# HVAL_TSAL.net
KiCad netlist of a schematic drawn in Altium Designer
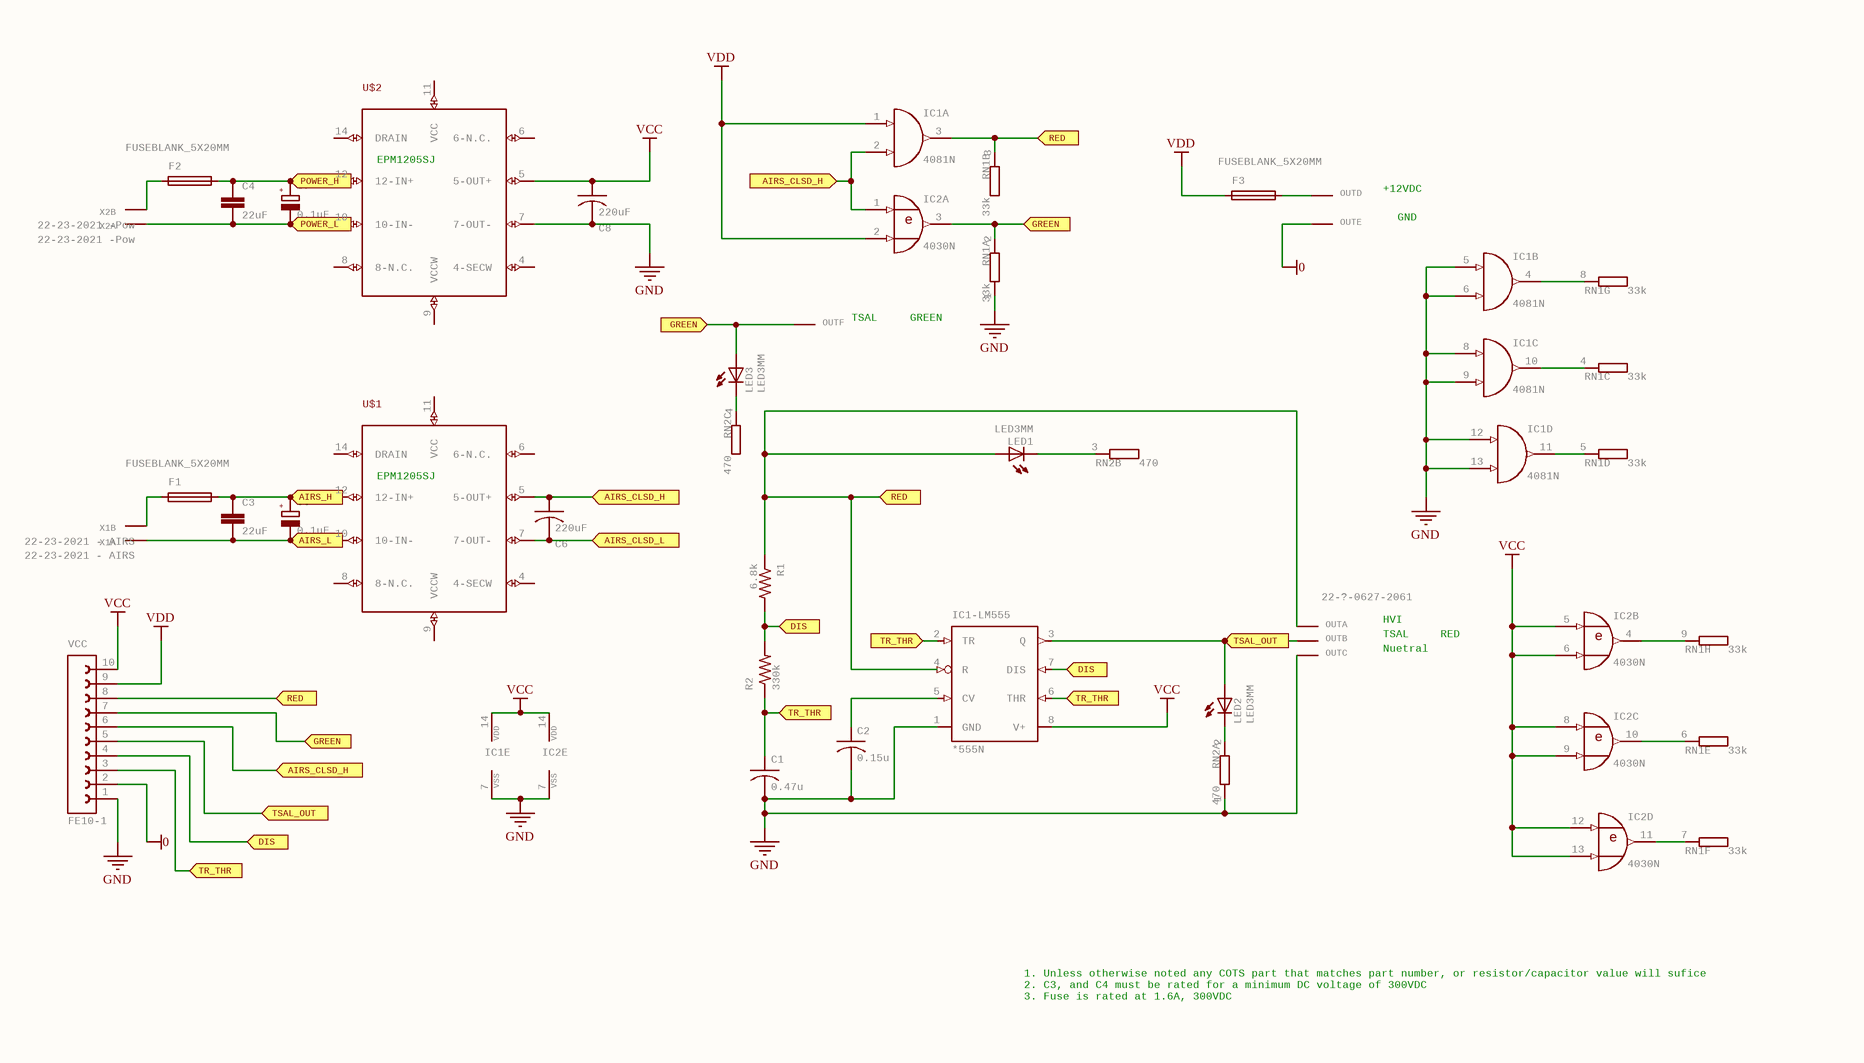
[diagram p0: HVAL_TSAL.SchDoc]

(export (version "E")
  (design (tool "Eeschema 10.0.6"))
  (components
    (comp (ref "C1")
      (value "0.47u")
      (footprint "C050-075X075")
      (description "CAPACITOR, American symbol")
      (libsource (lib "rcl") (part "C-US050-075X075"))
    )
    (comp (ref "C2")
      (value "0.15u")
      (footprint "C050-075X075")
      (description "CAPACITOR, American symbol")
      (libsource (lib "rcl") (part "C-US050-075X075"))
    )
    (comp (ref "C3")
      (value "22uF")
      (footprint "C150-091X182")
      (description "CAPACITOR, European symbol")
      (libsource (lib "rcl") (part "C-EU150-091X182"))
    )
    (comp (ref "C4")
      (value "22uF")
      (footprint "C150-091X182")
      (description "CAPACITOR, European symbol")
      (libsource (lib "rcl") (part "C-EU150-091X182"))
    )
    (comp (ref "C5")
      (value "0.1uF")
      (footprint "E7,5-16")
      (description "POLARIZED CAPACITOR, European symbol")
      (fields (field (name "+") "+"))
      (libsource (lib "rcl") (part "CPOL-EUE7.5-16"))
    )
    (comp (ref "C6")
      (value "220uF")
      (footprint "C050-055X075")
      (description "CAPACITOR, American symbol")
      (libsource (lib "rcl") (part "C-US050-055X075"))
    )
    (comp (ref "C7")
      (value "0.1uF")
      (footprint "E7,5-16")
      (description "POLARIZED CAPACITOR, European symbol")
      (fields (field (name "+") "+"))
      (libsource (lib "rcl") (part "CPOL-EUE7.5-16"))
    )
    (comp (ref "C8")
      (value "220uF")
      (footprint "C050-055X075")
      (description "CAPACITOR, American symbol")
      (libsource (lib "rcl") (part "C-US050-055X075"))
    )
    (comp (ref "F1")
      (value "FUSEBLANK_5X20MM")
      (footprint "FUSE_HOLDER_5X20MM")
      (description "Fuse")
      (fields (field (name "MF") "MF") (field (name "MPN") "MPN"))
      (libsource (lib "fuse") (part "FUSEBLANK_5X20MM"))
    )
    (comp (ref "F2")
      (value "FUSEBLANK_5X20MM")
      (footprint "FUSE_HOLDER_5X20MM")
      (description "Fuse")
      (fields (field (name "MF") "MF") (field (name "MPN") "MPN"))
      (libsource (lib "fuse") (part "FUSEBLANK_5X20MM"))
    )
    (comp (ref "F3")
      (value "FUSEBLANK_5X20MM")
      (footprint "FUSE_HOLDER_5X20MM")
      (description "Fuse")
      (fields (field (name "MF") "MF") (field (name "MPN") "MPN"))
      (libsource (lib "fuse") (part "FUSEBLANK_5X20MM"))
    )
    (comp (ref "IC1")
      (value "4081N")
      (footprint "DIL14")
      (description "Quad 2-input AND")
      (fields (field (name "VDD") "VDD") (field (name "VSS") "VSS"))
      (libsource (lib "40xx") (part "4081N"))
    )
    (comp (ref "IC1-LM555")
      (value "*555N")
      (footprint "DIL08")
      (description "TIMER")
      (libsource (lib "linear") (part "*555N"))
    )
    (comp (ref "IC2")
      (value "4030N")
      (footprint "DIL14")
      (description "Quad XOR")
      (fields (field (name "VDD") "VDD") (field (name "VSS") "VSS") (field (name "E") "e"))
      (libsource (lib "40xx") (part "4030N"))
    )
    (comp (ref "LED1") (value "LED3MM") (footprint "LED3MM") (libsource (lib "led") (part "LED3MM")))
    (comp (ref "LED2") (value "LED3MM") (footprint "LED3MM") (libsource (lib "led") (part "LED3MM")))
    (comp (ref "LED3") (value "LED3MM") (footprint "LED3MM") (libsource (lib "led") (part "LED3MM")))
    (comp (ref "OUT")
      (value "22-?-0627-2061")
      (footprint "6410-06")
      (description "CONNECTOR   wire to board 2.54 mm (.1 inch) pitch header")
      (fields (field (name "MF") "MOLEX") (field (name "MPN") "MPN"))
      (libsource (lib "con-molex") (part "22-?-0627-2061"))
    )
    (comp (ref "R1")
      (value "6.8k")
      (footprint "0309/12")
      (description "RESISTOR, American symbol")
      (libsource (lib "resistor") (part "R-US_0309/12"))
    )
    (comp (ref "R2")
      (value "330k")
      (footprint "0309/12")
      (description "RESISTOR, American symbol")
      (libsource (lib "resistor") (part "R-US_0309/12"))
    )
    (comp (ref "RN1")
      (value "33k")
      (footprint "SIL9")
      (description "SIL RESISTOR")
      (fields (field (name "MF") "MF") (field (name "MPN") "MPN"))
      (libsource (lib "resistor-sil") (part "GE08R"))
    )
    (comp (ref "RN2")
      (value "470")
      (footprint "SIL4")
      (description "SIL RESISTOR")
      (fields (field (name "MF") "MF") (field (name "MPN") "MPN"))
      (libsource (lib "resistor-sil") (part "GE03R"))
    )
    (comp (ref "U$1")
      (value "EPM1205SJ")
      (footprint "EPM1205SJ")
      (libsource (lib "DC-DC Converter") (part "EPM1205SJ"))
    )
    (comp (ref "U$2")
      (value "EPM1205SJ")
      (footprint "EPM1205SJ")
      (libsource (lib "DC-DC Converter") (part "EPM1205SJ"))
    )
    (comp (ref "VCC")
      (value "FE10-1")
      (footprint "FE10")
      (description "FEMALE HEADER")
      (fields (field (name "MF") "MF") (field (name "MPN") "MPN") (field (name "LIBRARYNAME") "con-lsta"))
      (libsource (lib "con-lsta") (part "FE10-1"))
    )
    (comp (ref "X1")
      (value "22-23-2021 - AIRS")
      (footprint "22-23-2021")
      (description ".100\" (2.54mm) Center Header - 2 Pin")
      (fields (field (name "MF") "MOLEX") (field (name "MPN") "22-23-2021"))
      (libsource (lib "con-molex") (part "22-23-2021"))
    )
    (comp (ref "X2")
      (value "22-23-2021 -Pow")
      (footprint "22-23-2021")
      (description ".100\" (2.54mm) Center Header - 2 Pin")
      (fields (field (name "MF") "MOLEX") (field (name "MPN") "22-23-2021"))
      (libsource (lib "con-molex") (part "22-23-2021"))
    )
  )
  (nets
    (net (code "1") (name "/AIRS_CLSD_H") (class "Default")
      (node (ref "C6") (pin "1") (pinfunction "1_1") (pintype "passive"))
      (node (ref "IC1") (pin "2") (pinfunction "I1_2") (pintype "input"))
      (node (ref "IC2") (pin "1") (pinfunction "I0_1") (pintype "input"))
      (node (ref "U$1") (pin "5") (pinfunction "5-OUT+_5") (pintype "bidirectional"))
      (node (ref "VCC") (pin "6") (pinfunction "6_6") (pintype "passive"))
    )
    (net (code "2") (name "/AIRS_CLSD_L") (class "Default")
      (node (ref "C6") (pin "2") (pinfunction "2_2") (pintype "passive"))
      (node (ref "U$1") (pin "7") (pinfunction "7-OUT-_7") (pintype "bidirectional"))
    )
    (net (code "3") (name "/AIRS_H") (class "Default")
      (node (ref "C3") (pin "1") (pinfunction "1_1") (pintype "passive"))
      (node (ref "C5") (pin "+") (pinfunction "+_+") (pintype "passive"))
      (node (ref "F1") (pin "2") (pinfunction "2_2") (pintype "passive"))
      (node (ref "U$1") (pin "12") (pinfunction "12-IN+_12") (pintype "bidirectional"))
    )
    (net (code "4") (name "/AIRS_L") (class "Default")
      (node (ref "C3") (pin "2") (pinfunction "2_2") (pintype "passive"))
      (node (ref "C5") (pin "-") (pinfunction "-_-") (pintype "passive"))
      (node (ref "U$1") (pin "10") (pinfunction "10-IN-_10") (pintype "bidirectional"))
      (node (ref "X1") (pin "1") (pinfunction "S_1") (pintype "passive"))
    )
    (net (code "5") (name "/DIS") (class "Default")
      (node (ref "IC1-LM555") (pin "7") (pinfunction "DIS_7") (pintype "input"))
      (node (ref "R1") (pin "2") (pinfunction "2_2") (pintype "passive"))
      (node (ref "R2") (pin "2") (pinfunction "2_2") (pintype "passive"))
      (node (ref "VCC") (pin "4") (pinfunction "4_4") (pintype "passive"))
    )
    (net (code "6") (name "/GREEN") (class "Default")
      (node (ref "IC2") (pin "3") (pinfunction "O_3") (pintype "output"))
      (node (ref "LED3") (pin "A") (pinfunction "A_A") (pintype "passive"))
      (node (ref "OUT") (pin "6") (pinfunction "S_6") (pintype "passive"))
      (node (ref "RN1") (pin "2") (pinfunction "2_2") (pintype "passive"))
      (node (ref "VCC") (pin "7") (pinfunction "7_7") (pintype "passive"))
    )
    (net (code "7") (name "/POWER_H") (class "Default")
      (node (ref "C4") (pin "1") (pinfunction "1_1") (pintype "passive"))
      (node (ref "C7") (pin "+") (pinfunction "+_+") (pintype "passive"))
      (node (ref "F2") (pin "2") (pinfunction "2_2") (pintype "passive"))
      (node (ref "U$2") (pin "12") (pinfunction "12-IN+_12") (pintype "bidirectional"))
    )
    (net (code "8") (name "/POWER_L") (class "Default")
      (node (ref "C4") (pin "2") (pinfunction "2_2") (pintype "passive"))
      (node (ref "C7") (pin "-") (pinfunction "-_-") (pintype "passive"))
      (node (ref "U$2") (pin "10") (pinfunction "10-IN-_10") (pintype "bidirectional"))
      (node (ref "X2") (pin "1") (pinfunction "S_1") (pintype "passive"))
    )
    (net (code "9") (name "/RED") (class "Default")
      (node (ref "IC1") (pin "3") (pinfunction "O_3") (pintype "output"))
      (node (ref "IC1-LM555") (pin "4") (pinfunction "R_4") (pintype "input"))
      (node (ref "LED1") (pin "A") (pinfunction "A_A") (pintype "passive"))
      (node (ref "OUT") (pin "1") (pinfunction "S_1") (pintype "passive"))
      (node (ref "R1") (pin "1") (pinfunction "1_1") (pintype "passive"))
      (node (ref "RN1") (pin "3") (pinfunction "2_3") (pintype "passive"))
      (node (ref "VCC") (pin "8") (pinfunction "8_8") (pintype "passive"))
    )
    (net (code "10") (name "/TR_THR") (class "Default")
      (node (ref "C1") (pin "1") (pinfunction "1_1") (pintype "passive"))
      (node (ref "IC1-LM555") (pin "2") (pinfunction "TR_2") (pintype "input"))
      (node (ref "IC1-LM555") (pin "6") (pinfunction "THR_6") (pintype "input"))
      (node (ref "R2") (pin "1") (pinfunction "1_1") (pintype "passive"))
      (node (ref "VCC") (pin "3") (pinfunction "3_3") (pintype "passive"))
    )
    (net (code "11") (name "/TSAL_OUT") (class "Default")
      (node (ref "IC1-LM555") (pin "3") (pinfunction "Q_3") (pintype "output"))
      (node (ref "LED2") (pin "A") (pinfunction "A_A") (pintype "passive"))
      (node (ref "OUT") (pin "2") (pinfunction "S_2") (pintype "passive"))
      (node (ref "VCC") (pin "5") (pinfunction "5_5") (pintype "passive"))
    )
    (net (code "12") (name "0") (class "Default")
      (node (ref "OUT") (pin "5") (pinfunction "S_5") (pintype "passive"))
      (node (ref "VCC") (pin "2") (pinfunction "2_2") (pintype "passive"))
    )
    (net (code "13") (name "GND") (class "Default")
      (node (ref "C1") (pin "2") (pinfunction "2_2") (pintype "passive"))
      (node (ref "C2") (pin "2") (pinfunction "2_2") (pintype "passive"))
      (node (ref "C8") (pin "2") (pinfunction "2_2") (pintype "passive"))
      (node (ref "IC1") (pin "12") (pinfunction "I0_12") (pintype "input"))
      (node (ref "IC1") (pin "13") (pinfunction "I1_13") (pintype "input"))
      (node (ref "IC1") (pin "5") (pinfunction "I0_5") (pintype "input"))
      (node (ref "IC1") (pin "6") (pinfunction "I1_6") (pintype "input"))
      (node (ref "IC1") (pin "7") (pinfunction "VSS_7") (pintype "power_in"))
      (node (ref "IC1") (pin "8") (pinfunction "I0_8") (pintype "input"))
      (node (ref "IC1") (pin "9") (pinfunction "I1_9") (pintype "input"))
      (node (ref "IC1-LM555") (pin "1") (pinfunction "GND_1") (pintype "power_in"))
      (node (ref "IC2") (pin "7") (pinfunction "VSS_7") (pintype "power_in"))
      (node (ref "OUT") (pin "3") (pinfunction "S_3") (pintype "passive"))
      (node (ref "RN1") (pin "1") (pinfunction "1_1") (pintype "passive"))
      (node (ref "RN2") (pin "1") (pinfunction "1_1") (pintype "passive"))
      (node (ref "U$2") (pin "7") (pinfunction "7-OUT-_7") (pintype "bidirectional"))
      (node (ref "VCC") (pin "1") (pinfunction "1_1") (pintype "passive"))
    )
    (net (code "14") (name "Net-(IC1-LM555-CV)") (class "Default")
      (node (ref "C2") (pin "1") (pinfunction "1_1") (pintype "passive"))
      (node (ref "IC1-LM555") (pin "5") (pinfunction "CV_5") (pintype "input"))
    )
    (net (code "15") (name "Net-(IC1B-O)") (class "Default")
      (node (ref "IC1") (pin "4") (pinfunction "O_4") (pintype "output"))
      (node (ref "RN1") (pin "8") (pinfunction "2_8") (pintype "passive"))
    )
    (net (code "16") (name "Net-(IC1C-O)") (class "Default")
      (node (ref "IC1") (pin "10") (pinfunction "O_10") (pintype "output"))
      (node (ref "RN1") (pin "4") (pinfunction "2_4") (pintype "passive"))
    )
    (net (code "17") (name "Net-(IC1D-O)") (class "Default")
      (node (ref "IC1") (pin "11") (pinfunction "O_11") (pintype "output"))
      (node (ref "RN1") (pin "5") (pinfunction "2_5") (pintype "passive"))
    )
    (net (code "18") (name "Net-(IC2B-O)") (class "Default")
      (node (ref "IC2") (pin "4") (pinfunction "O_4") (pintype "output"))
      (node (ref "RN1") (pin "9") (pinfunction "2_9") (pintype "passive"))
    )
    (net (code "19") (name "Net-(IC2C-O)") (class "Default")
      (node (ref "IC2") (pin "10") (pinfunction "O_10") (pintype "output"))
      (node (ref "RN1") (pin "6") (pinfunction "2_6") (pintype "passive"))
    )
    (net (code "20") (name "Net-(IC2D-O)") (class "Default")
      (node (ref "IC2") (pin "11") (pinfunction "O_11") (pintype "output"))
      (node (ref "RN1") (pin "7") (pinfunction "2_7") (pintype "passive"))
    )
    (net (code "21") (name "Net-(LED1-C)") (class "Default")
      (node (ref "LED1") (pin "K") (pinfunction "C_K") (pintype "passive"))
      (node (ref "RN2") (pin "3") (pinfunction "2_3") (pintype "passive"))
    )
    (net (code "22") (name "Net-(LED2-C)") (class "Default")
      (node (ref "LED2") (pin "K") (pinfunction "C_K") (pintype "passive"))
      (node (ref "RN2") (pin "2") (pinfunction "2_2") (pintype "passive"))
    )
    (net (code "23") (name "Net-(LED3-C)") (class "Default")
      (node (ref "LED3") (pin "K") (pinfunction "C_K") (pintype "passive"))
      (node (ref "RN2") (pin "4") (pinfunction "2_4") (pintype "passive"))
    )
    (net (code "24") (name "Net-(OUTD-S)") (class "Default")
      (node (ref "F3") (pin "2") (pinfunction "2_2") (pintype "passive"))
      (node (ref "OUT") (pin "4") (pinfunction "S_4") (pintype "passive"))
    )
    (net (code "25") (name "Net-(X1B-S)") (class "Default")
      (node (ref "F1") (pin "1") (pinfunction "1_1") (pintype "passive"))
      (node (ref "X1") (pin "2") (pinfunction "S_2") (pintype "passive"))
    )
    (net (code "26") (name "Net-(X2B-S)") (class "Default")
      (node (ref "F2") (pin "1") (pinfunction "1_1") (pintype "passive"))
      (node (ref "X2") (pin "2") (pinfunction "S_2") (pintype "passive"))
    )
    (net (code "27") (name "VCC") (class "Default")
      (node (ref "C8") (pin "1") (pinfunction "1_1") (pintype "passive"))
      (node (ref "IC1") (pin "14") (pinfunction "VDD_14") (pintype "power_in"))
      (node (ref "IC1-LM555") (pin "8") (pinfunction "V+_8") (pintype "power_in"))
      (node (ref "IC2") (pin "12") (pinfunction "I0_12") (pintype "input"))
      (node (ref "IC2") (pin "13") (pinfunction "I1_13") (pintype "input"))
      (node (ref "IC2") (pin "14") (pinfunction "VDD_14") (pintype "power_in"))
      (node (ref "IC2") (pin "5") (pinfunction "I0_5") (pintype "input"))
      (node (ref "IC2") (pin "6") (pinfunction "I1_6") (pintype "input"))
      (node (ref "IC2") (pin "8") (pinfunction "I0_8") (pintype "input"))
      (node (ref "IC2") (pin "9") (pinfunction "I1_9") (pintype "input"))
      (node (ref "U$2") (pin "5") (pinfunction "5-OUT+_5") (pintype "bidirectional"))
      (node (ref "VCC") (pin "10") (pinfunction "10_10") (pintype "passive"))
    )
    (net (code "28") (name "VDD") (class "Default")
      (node (ref "F3") (pin "1") (pinfunction "1_1") (pintype "passive"))
      (node (ref "IC1") (pin "1") (pinfunction "I0_1") (pintype "input"))
      (node (ref "IC2") (pin "2") (pinfunction "I1_2") (pintype "input"))
      (node (ref "VCC") (pin "9") (pinfunction "9_9") (pintype "passive"))
    )
    (net (code "29") (name "unconnected-(U$1-4-SECW-Pad4)") (class "Default")
      (node (ref "U$1") (pin "4") (pinfunction "4-SECW_4") (pintype "bidirectional"))
    )
    (net (code "30") (name "unconnected-(U$1-6-N.C.-Pad6)") (class "Default")
      (node (ref "U$1") (pin "6") (pinfunction "6-N.C._6") (pintype "bidirectional"))
    )
    (net (code "31") (name "unconnected-(U$1-8-N.C.-Pad8)") (class "Default")
      (node (ref "U$1") (pin "8") (pinfunction "8-N.C._8") (pintype "bidirectional"))
    )
    (net (code "32") (name "unconnected-(U$1-DRAIN-Pad14)") (class "Default")
      (node (ref "U$1") (pin "14") (pinfunction "DRAIN_14") (pintype "bidirectional"))
    )
    (net (code "33") (name "unconnected-(U$1-VCC-Pad11)") (class "Default")
      (node (ref "U$1") (pin "11") (pinfunction "VCC_11") (pintype "bidirectional"))
    )
    (net (code "34") (name "unconnected-(U$1-VCCW-Pad9)") (class "Default")
      (node (ref "U$1") (pin "9") (pinfunction "VCCW_9") (pintype "bidirectional"))
    )
    (net (code "35") (name "unconnected-(U$2-4-SECW-Pad4)") (class "Default")
      (node (ref "U$2") (pin "4") (pinfunction "4-SECW_4") (pintype "bidirectional"))
    )
    (net (code "36") (name "unconnected-(U$2-6-N.C.-Pad6)") (class "Default")
      (node (ref "U$2") (pin "6") (pinfunction "6-N.C._6") (pintype "bidirectional"))
    )
    (net (code "37") (name "unconnected-(U$2-8-N.C.-Pad8)") (class "Default")
      (node (ref "U$2") (pin "8") (pinfunction "8-N.C._8") (pintype "bidirectional"))
    )
    (net (code "38") (name "unconnected-(U$2-DRAIN-Pad14)") (class "Default")
      (node (ref "U$2") (pin "14") (pinfunction "DRAIN_14") (pintype "bidirectional"))
    )
    (net (code "39") (name "unconnected-(U$2-VCC-Pad11)") (class "Default")
      (node (ref "U$2") (pin "11") (pinfunction "VCC_11") (pintype "bidirectional"))
    )
    (net (code "40") (name "unconnected-(U$2-VCCW-Pad9)") (class "Default")
      (node (ref "U$2") (pin "9") (pinfunction "VCCW_9") (pintype "bidirectional"))
    )
  )
)
